# Main_Titan_V3.net
KiCad netlist of a schematic drawn in EAGLE
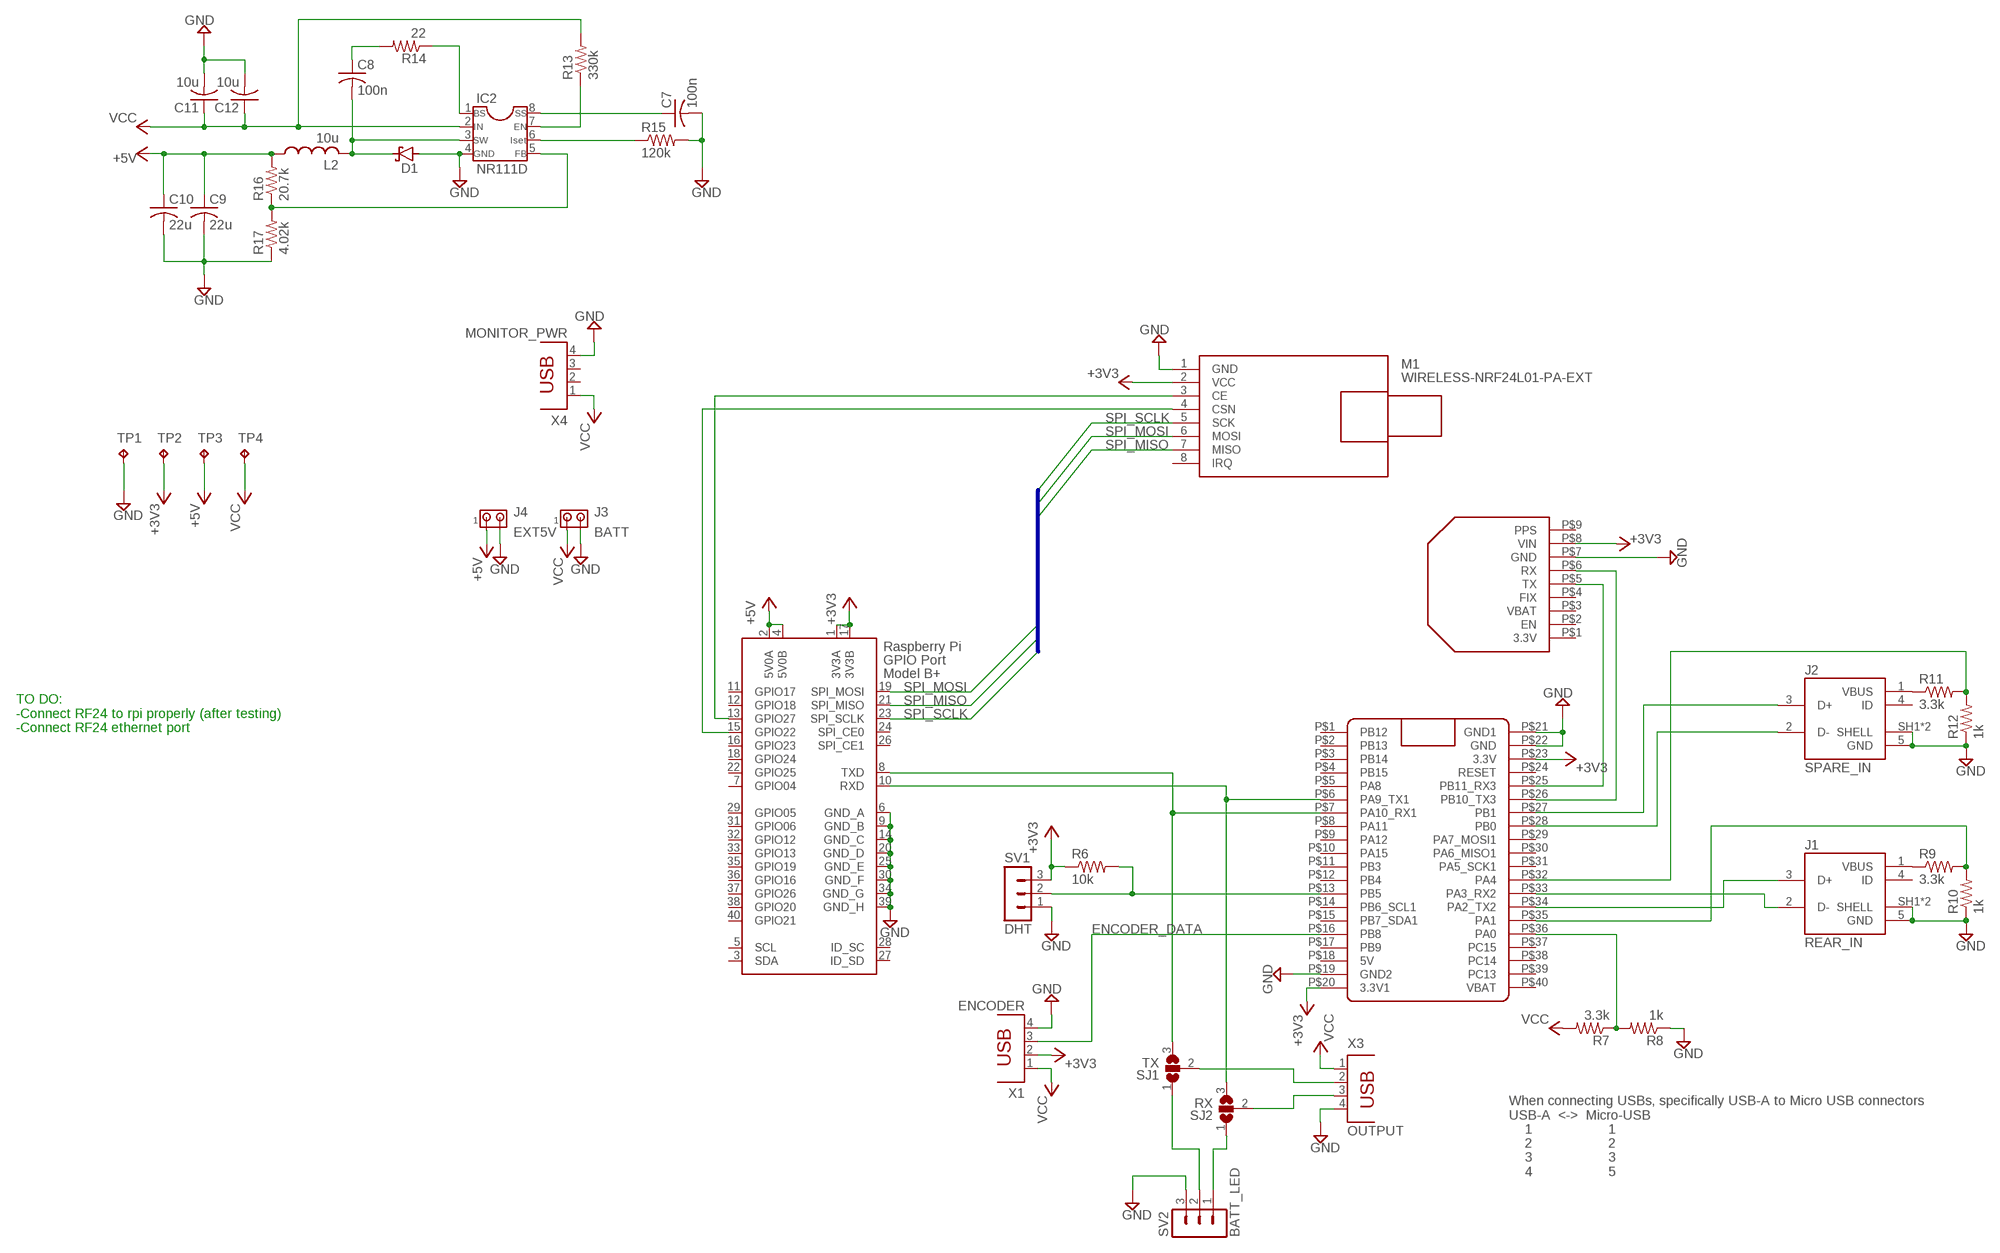
[diagram p0: schematic, sheet 1]

(export (version "E")
  (design (tool "Eeschema 10.0.6"))
  (components
    (comp (ref "C7")
      (value "100n")
      (footprint "eagle-import:C050-024X044")
      (libsource (lib "eagle-import") (part "C-US050-024X044"))
    )
    (comp (ref "C8")
      (value "100n")
      (footprint "eagle-import:C050-024X044")
      (libsource (lib "eagle-import") (part "C-US050-024X044"))
    )
    (comp (ref "C9")
      (value "22u")
      (footprint "eagle-import:C025-024X044")
      (libsource (lib "eagle-import") (part "C-US025-024X044"))
    )
    (comp (ref "C10")
      (value "22u")
      (footprint "eagle-import:C025-024X044")
      (libsource (lib "eagle-import") (part "C-US025-024X044"))
    )
    (comp (ref "C11")
      (value "10u")
      (footprint "eagle-import:C025-024X044")
      (libsource (lib "eagle-import") (part "C-US025-024X044"))
    )
    (comp (ref "C12")
      (value "10u")
      (footprint "eagle-import:C025-024X044")
      (libsource (lib "eagle-import") (part "C-US025-024X044"))
    )
    (comp (ref "D1")
      (value "SCHOTTKY-DIODEC4111-15")
      (footprint "eagle-import:C4111-15")
      (libsource (lib "eagle-import") (part "SCHOTTKY-DIODEC4111-15"))
    )
    (comp (ref "IC2")
      (value "NR111D")
      (footprint "eagle-import:DIL08")
      (libsource (lib "eagle-import") (part "DIL8"))
    )
    (comp (ref "J1")
      (value "REAR_IN")
      (footprint "eagle-import:TE_2172034-1")
      (fields
        (field (name "COMMENT") "2172034-1")
        (field (name "DIGI-KEY_PART_NUMBER") "A135698-ND")
        (field (name "MF") "TE Connectivity")
      )
      (libsource (lib "eagle-import") (part "2172034-1"))
    )
    (comp (ref "J2")
      (value "SPARE_IN")
      (footprint "eagle-import:TE_2172034-1")
      (fields
        (field (name "COMMENT") "2172034-1")
        (field (name "DIGI-KEY_PART_NUMBER") "A135698-ND")
        (field (name "MF") "TE Connectivity")
      )
      (libsource (lib "eagle-import") (part "2172034-1"))
    )
    (comp (ref "J3")
      (value "BATT")
      (footprint "eagle-import:1X2MTA")
      (libsource (lib "eagle-import") (part "MTA02-156"))
    )
    (comp (ref "J4")
      (value "EXT5V")
      (footprint "eagle-import:1X2MTA")
      (libsource (lib "eagle-import") (part "MTA02-156"))
    )
    (comp (ref "L2")
      (value "10u")
      (footprint "eagle-import:INDRD650W105D880H1100B")
      (libsource (lib "eagle-import") (part "WURTHINDUCTOR1"))
    )
    (comp (ref "M1")
      (value "WIRELESS-NRF24L01-PA-EXT")
      (footprint "eagle-import:WIRELESS-NRF24L01-PA-EXT")
      (libsource (lib "eagle-import") (part "WIRELESS-NRF24L01-PA-EXT"))
    )
    (comp (ref "R6")
      (value "10k")
      (footprint "eagle-import:0204_7")
      (libsource (lib "eagle-import") (part "R-US_0204/7"))
    )
    (comp (ref "R7")
      (value "3.3k")
      (footprint "eagle-import:0204_7")
      (libsource (lib "eagle-import") (part "R-US_0204/7"))
    )
    (comp (ref "R8")
      (value "1k")
      (footprint "eagle-import:0204_7")
      (libsource (lib "eagle-import") (part "R-US_0204/7"))
    )
    (comp (ref "R9")
      (value "3.3k")
      (footprint "eagle-import:0204_7")
      (libsource (lib "eagle-import") (part "R-US_0204/7"))
    )
    (comp (ref "R10")
      (value "1k")
      (footprint "eagle-import:0204_7")
      (libsource (lib "eagle-import") (part "R-US_0204/7"))
    )
    (comp (ref "R11")
      (value "3.3k")
      (footprint "eagle-import:0204_7")
      (libsource (lib "eagle-import") (part "R-US_0204/7"))
    )
    (comp (ref "R12")
      (value "1k")
      (footprint "eagle-import:0204_7")
      (libsource (lib "eagle-import") (part "R-US_0204/7"))
    )
    (comp (ref "R13")
      (value "330k")
      (footprint "eagle-import:0204_7")
      (libsource (lib "eagle-import") (part "R-US_0204/7"))
    )
    (comp (ref "R14")
      (value "22")
      (footprint "eagle-import:0204_7")
      (libsource (lib "eagle-import") (part "R-US_0204/7"))
    )
    (comp (ref "R15")
      (value "120k")
      (footprint "eagle-import:0204_7")
      (libsource (lib "eagle-import") (part "R-US_0204/7"))
    )
    (comp (ref "R16")
      (value "20.7k")
      (footprint "eagle-import:0204_7")
      (libsource (lib "eagle-import") (part "R-US_0204/7"))
    )
    (comp (ref "R17")
      (value "4.02k")
      (footprint "eagle-import:0204_7")
      (libsource (lib "eagle-import") (part "R-US_0204/7"))
    )
    (comp (ref "SJ1")
      (value "TX")
      (footprint "eagle-import:SJ_2")
      (libsource (lib "eagle-import") (part "SJ2W"))
    )
    (comp (ref "SJ2")
      (value "RX")
      (footprint "eagle-import:SJ_2")
      (libsource (lib "eagle-import") (part "SJ2W"))
    )
    (comp (ref "SV1")
      (value "DHT")
      (footprint "eagle-import:MA03-1")
      (libsource (lib "eagle-import") (part "MA03-1"))
    )
    (comp (ref "SV2")
      (value "BATT_LED")
      (footprint "eagle-import:MA03-1")
      (libsource (lib "eagle-import") (part "MA03-1"))
    )
    (comp (ref "TP1")
      (value "GND")
      (footprint "eagle-import:TP20SQ")
      (libsource (lib "eagle-import") (part "TPTP20SQ"))
    )
    (comp (ref "TP2")
      (value "3V3")
      (footprint "eagle-import:TP20SQ")
      (libsource (lib "eagle-import") (part "TPTP20SQ"))
    )
    (comp (ref "TP3")
      (value "5V")
      (footprint "eagle-import:TP20SQ")
      (libsource (lib "eagle-import") (part "TPTP20SQ"))
    )
    (comp (ref "TP4")
      (value "BAT")
      (footprint "eagle-import:TP20SQ")
      (libsource (lib "eagle-import") (part "TPTP20SQ"))
    )
    (comp (ref "U$1")
      (value "BLUE_PILL")
      (footprint "eagle-import:BLUE_PILL")
      (libsource (lib "eagle-import") (part "BLUE_PILL"))
    )
    (comp (ref "U$2")
      (value "ULTIMATE-GPS")
      (footprint "eagle-import:ULTIMATE_GPS")
      (libsource (lib "eagle-import") (part "ULTIMATE-GPS"))
    )
    (comp (ref "X1")
      (value "ENCODER")
      (footprint "eagle-import:PN87520")
      (libsource (lib "eagle-import") (part "PN87520"))
    )
    (comp (ref "X2")
      (value "RPI")
      (footprint "eagle-import:RASPI_GPIO_B+_BOX")
      (libsource (lib "eagle-import") (part "RASPI_GPIO_B+#_BOX"))
    )
    (comp (ref "X3")
      (value "OUTPUT")
      (footprint "eagle-import:PN87520")
      (libsource (lib "eagle-import") (part "PN87520"))
    )
    (comp (ref "X4")
      (value "MONITOR_PWR")
      (footprint "eagle-import:PN87520")
      (libsource (lib "eagle-import") (part "PN87520"))
    )
  )
  (nets
    (net (code "1") (name "+3V3") (class "Default")
      (node (ref "M1") (pin "2") (pinfunction "VCC_2") (pintype "power_in"))
      (node (ref "R6") (pin "1") (pinfunction "1_1") (pintype "passive"))
      (node (ref "SV1") (pin "3") (pinfunction "3_3") (pintype "passive"))
      (node (ref "TP2") (pin "TP") (pinfunction "TP_TP") (pintype "input"))
      (node (ref "U$1") (pin "P$20") (pinfunction "3.3V1_P$20") (pintype "power_in"))
      (node (ref "U$1") (pin "P$23") (pinfunction "3.3V_P$23") (pintype "power_in"))
      (node (ref "U$2") (pin "P$8") (pinfunction "VIN_P$8") (pintype "bidirectional"))
      (node (ref "X1") (pin "2") (pinfunction "2_2") (pintype "passive"))
      (node (ref "X2") (pin "1") (pinfunction "3V3A_1") (pintype "power_in"))
      (node (ref "X2") (pin "17") (pinfunction "3V3B_17") (pintype "power_in"))
    )
    (net (code "2") (name "+5V") (class "Default")
      (node (ref "C10") (pin "1") (pinfunction "1_1") (pintype "passive"))
      (node (ref "C9") (pin "1") (pinfunction "1_1") (pintype "passive"))
      (node (ref "J4") (pin "1") (pinfunction "1_1") (pintype "passive"))
      (node (ref "L2") (pin "1") (pinfunction "1_1") (pintype "passive"))
      (node (ref "R16") (pin "2") (pinfunction "2_2") (pintype "passive"))
      (node (ref "TP3") (pin "TP") (pinfunction "TP_TP") (pintype "input"))
      (node (ref "X2") (pin "2") (pinfunction "5V0A_2") (pintype "power_in"))
      (node (ref "X2") (pin "4") (pinfunction "5V0B_4") (pintype "power_in"))
    )
    (net (code "3") (name "/3.3V") (class "Default")
      (node (ref "U$2") (pin "P$1") (pinfunction "3.3V_P$1") (pintype "power_in"))
    )
    (net (code "4") (name "/ENCODER_DATA") (class "Default")
      (node (ref "U$1") (pin "P$16") (pinfunction "PB8_P$16") (pintype "bidirectional"))
      (node (ref "X1") (pin "3") (pinfunction "3_3") (pintype "passive"))
    )
    (net (code "5") (name "/SPI_MISO") (class "Default")
      (node (ref "M1") (pin "7") (pinfunction "MISO_7") (pintype "bidirectional"))
      (node (ref "X2") (pin "21") (pinfunction "SPI_MISO_21") (pintype "bidirectional"))
    )
    (net (code "6") (name "/SPI_MOSI") (class "Default")
      (node (ref "M1") (pin "6") (pinfunction "MOSI_6") (pintype "bidirectional"))
      (node (ref "X2") (pin "19") (pinfunction "SPI_MOSI_19") (pintype "bidirectional"))
    )
    (net (code "7") (name "/SPI_SCLK") (class "Default")
      (node (ref "M1") (pin "5") (pinfunction "SCK_5") (pintype "bidirectional"))
      (node (ref "X2") (pin "23") (pinfunction "SPI_SCLK_23") (pintype "bidirectional"))
    )
    (net (code "8") (name "GND") (class "Default")
      (node (ref "C10") (pin "2") (pinfunction "2_2") (pintype "passive"))
      (node (ref "C11") (pin "2") (pinfunction "2_2") (pintype "passive"))
      (node (ref "C12") (pin "2") (pinfunction "2_2") (pintype "passive"))
      (node (ref "C7") (pin "2") (pinfunction "2_2") (pintype "passive"))
      (node (ref "C9") (pin "2") (pinfunction "2_2") (pintype "passive"))
      (node (ref "D1") (pin "A") (pinfunction "A_A") (pintype "passive"))
      (node (ref "IC2") (pin "4") (pinfunction "GND_4") (pintype "passive"))
      (node (ref "J1") (pin "5") (pinfunction "GND_5") (pintype "power_in"))
      (node (ref "J1") (pin "SH1") (pinfunction "SHELL_SH1") (pintype "power_in"))
      (node (ref "J1") (pin "SH2") (pinfunction "SHELL_SH2") (pintype "power_in"))
      (node (ref "J2") (pin "5") (pinfunction "GND_5") (pintype "power_in"))
      (node (ref "J2") (pin "SH1") (pinfunction "SHELL_SH1") (pintype "power_in"))
      (node (ref "J2") (pin "SH2") (pinfunction "SHELL_SH2") (pintype "power_in"))
      (node (ref "J3") (pin "2") (pinfunction "2_2") (pintype "passive"))
      (node (ref "J4") (pin "2") (pinfunction "2_2") (pintype "passive"))
      (node (ref "M1") (pin "1") (pinfunction "GND_1") (pintype "power_in"))
      (node (ref "R10") (pin "1") (pinfunction "1_1") (pintype "passive"))
      (node (ref "R12") (pin "1") (pinfunction "1_1") (pintype "passive"))
      (node (ref "R15") (pin "2") (pinfunction "2_2") (pintype "passive"))
      (node (ref "R17") (pin "1") (pinfunction "1_1") (pintype "passive"))
      (node (ref "R8") (pin "1") (pinfunction "1_1") (pintype "passive"))
      (node (ref "SV1") (pin "1") (pinfunction "1_1") (pintype "passive"))
      (node (ref "SV2") (pin "3") (pinfunction "3_3") (pintype "passive"))
      (node (ref "TP1") (pin "TP") (pinfunction "TP_TP") (pintype "input"))
      (node (ref "U$1") (pin "P$19") (pinfunction "GND2_P$19") (pintype "bidirectional"))
      (node (ref "U$1") (pin "P$21") (pinfunction "GND1_P$21") (pintype "power_in"))
      (node (ref "U$1") (pin "P$22") (pinfunction "GND_P$22") (pintype "bidirectional"))
      (node (ref "U$2") (pin "P$7") (pinfunction "GND_P$7") (pintype "power_in"))
      (node (ref "X1") (pin "4") (pinfunction "4_4") (pintype "passive"))
      (node (ref "X2") (pin "14") (pinfunction "GND_C_14") (pintype "power_in"))
      (node (ref "X2") (pin "20") (pinfunction "GND_D_20") (pintype "power_in"))
      (node (ref "X2") (pin "25") (pinfunction "GND_E_25") (pintype "power_in"))
      (node (ref "X2") (pin "30") (pinfunction "GND_F_30") (pintype "power_in"))
      (node (ref "X2") (pin "34") (pinfunction "GND_G_34") (pintype "power_in"))
      (node (ref "X2") (pin "39") (pinfunction "GND_H_39") (pintype "power_in"))
      (node (ref "X2") (pin "6") (pinfunction "GND_A_6") (pintype "power_in"))
      (node (ref "X2") (pin "9") (pinfunction "GND_B_9") (pintype "power_in"))
      (node (ref "X3") (pin "4") (pinfunction "4_4") (pintype "passive"))
      (node (ref "X4") (pin "4") (pinfunction "4_4") (pintype "passive"))
    )
    (net (code "9") (name "Net-(C8-Pad1)") (class "Default")
      (node (ref "C8") (pin "1") (pinfunction "1_1") (pintype "passive"))
      (node (ref "R14") (pin "2") (pinfunction "2_2") (pintype "passive"))
    )
    (net (code "10") (name "Net-(IC2-BS)") (class "Default")
      (node (ref "IC2") (pin "1") (pinfunction "BS_1") (pintype "passive"))
      (node (ref "R14") (pin "1") (pinfunction "1_1") (pintype "passive"))
    )
    (net (code "11") (name "Net-(IC2-EN)") (class "Default")
      (node (ref "IC2") (pin "7") (pinfunction "EN_7") (pintype "passive"))
      (node (ref "R13") (pin "1") (pinfunction "1_1") (pintype "passive"))
    )
    (net (code "12") (name "Net-(IC2-FB)") (class "Default")
      (node (ref "IC2") (pin "5") (pinfunction "FB_5") (pintype "passive"))
      (node (ref "R16") (pin "1") (pinfunction "1_1") (pintype "passive"))
      (node (ref "R17") (pin "2") (pinfunction "2_2") (pintype "passive"))
    )
    (net (code "13") (name "Net-(IC2-ISET)") (class "Default")
      (node (ref "IC2") (pin "6") (pinfunction "ISET_6") (pintype "passive"))
      (node (ref "R15") (pin "1") (pinfunction "1_1") (pintype "passive"))
    )
    (net (code "14") (name "Net-(IC2-SS)") (class "Default")
      (node (ref "C7") (pin "1") (pinfunction "1_1") (pintype "passive"))
      (node (ref "IC2") (pin "8") (pinfunction "SS_8") (pintype "passive"))
    )
    (net (code "15") (name "Net-(IC2-SW)") (class "Default")
      (node (ref "C8") (pin "2") (pinfunction "2_2") (pintype "passive"))
      (node (ref "D1") (pin "C") (pinfunction "C_C") (pintype "passive"))
      (node (ref "IC2") (pin "3") (pinfunction "SW_3") (pintype "passive"))
      (node (ref "L2") (pin "2") (pinfunction "2_2") (pintype "passive"))
    )
    (net (code "16") (name "Net-(J1-D+)") (class "Default")
      (node (ref "J1") (pin "3") (pinfunction "D+_3") (pintype "bidirectional"))
      (node (ref "U$1") (pin "P$34") (pinfunction "PA2_TX2_P$34") (pintype "bidirectional"))
    )
    (net (code "17") (name "Net-(J1-D-)") (class "Default")
      (node (ref "J1") (pin "2") (pinfunction "D-_2") (pintype "bidirectional"))
      (node (ref "U$1") (pin "P$33") (pinfunction "PA3_RX2_P$33") (pintype "bidirectional"))
    )
    (net (code "18") (name "Net-(J1-VBUS)") (class "Default")
      (node (ref "J1") (pin "1") (pinfunction "VBUS_1") (pintype "power_in"))
      (node (ref "R9") (pin "1") (pinfunction "1_1") (pintype "passive"))
    )
    (net (code "19") (name "Net-(J2-D+)") (class "Default")
      (node (ref "J2") (pin "3") (pinfunction "D+_3") (pintype "bidirectional"))
      (node (ref "U$1") (pin "P$27") (pinfunction "PB1_P$27") (pintype "bidirectional"))
    )
    (net (code "20") (name "Net-(J2-D-)") (class "Default")
      (node (ref "J2") (pin "2") (pinfunction "D-_2") (pintype "bidirectional"))
      (node (ref "U$1") (pin "P$28") (pinfunction "PB0_P$28") (pintype "bidirectional"))
    )
    (net (code "21") (name "Net-(J2-VBUS)") (class "Default")
      (node (ref "J2") (pin "1") (pinfunction "VBUS_1") (pintype "power_in"))
      (node (ref "R11") (pin "1") (pinfunction "1_1") (pintype "passive"))
    )
    (net (code "22") (name "Net-(M1-CE)") (class "Default")
      (node (ref "M1") (pin "3") (pinfunction "CE_3") (pintype "bidirectional"))
      (node (ref "X2") (pin "13") (pinfunction "GPIO27_13") (pintype "bidirectional"))
    )
    (net (code "23") (name "Net-(M1-CSN)") (class "Default")
      (node (ref "M1") (pin "4") (pinfunction "CSN_4") (pintype "bidirectional"))
      (node (ref "X2") (pin "15") (pinfunction "GPIO22_15") (pintype "bidirectional"))
    )
    (net (code "24") (name "Net-(SJ1-Pad1)") (class "Default")
      (node (ref "SJ1") (pin "1") (pinfunction "1_1") (pintype "passive"))
      (node (ref "SV2") (pin "2") (pinfunction "2_2") (pintype "passive"))
    )
    (net (code "25") (name "Net-(SJ1-Pad2)") (class "Default")
      (node (ref "SJ1") (pin "2") (pinfunction "2_2") (pintype "passive"))
      (node (ref "X3") (pin "2") (pinfunction "2_2") (pintype "passive"))
    )
    (net (code "26") (name "Net-(SJ2-Pad1)") (class "Default")
      (node (ref "SJ2") (pin "1") (pinfunction "1_1") (pintype "passive"))
      (node (ref "SV2") (pin "1") (pinfunction "1_1") (pintype "passive"))
    )
    (net (code "27") (name "Net-(SJ2-Pad2)") (class "Default")
      (node (ref "SJ2") (pin "2") (pinfunction "2_2") (pintype "passive"))
      (node (ref "X3") (pin "3") (pinfunction "3_3") (pintype "passive"))
    )
    (net (code "28") (name "Net-(U$1-PA0)") (class "Default")
      (node (ref "R7") (pin "1") (pinfunction "1_1") (pintype "passive"))
      (node (ref "R8") (pin "2") (pinfunction "2_2") (pintype "passive"))
      (node (ref "U$1") (pin "P$36") (pinfunction "PA0_P$36") (pintype "bidirectional"))
    )
    (net (code "29") (name "Net-(U$1-PA1)") (class "Default")
      (node (ref "R10") (pin "2") (pinfunction "2_2") (pintype "passive"))
      (node (ref "R9") (pin "2") (pinfunction "2_2") (pintype "passive"))
      (node (ref "U$1") (pin "P$35") (pinfunction "PA1_P$35") (pintype "bidirectional"))
    )
    (net (code "30") (name "Net-(U$1-PA4)") (class "Default")
      (node (ref "R11") (pin "2") (pinfunction "2_2") (pintype "passive"))
      (node (ref "R12") (pin "2") (pinfunction "2_2") (pintype "passive"))
      (node (ref "U$1") (pin "P$32") (pinfunction "PA4_P$32") (pintype "bidirectional"))
    )
    (net (code "31") (name "Net-(U$1-PA9_TX1)") (class "Default")
      (node (ref "SJ2") (pin "3") (pinfunction "3_3") (pintype "passive"))
      (node (ref "U$1") (pin "P$6") (pinfunction "PA9_TX1_P$6") (pintype "bidirectional"))
      (node (ref "X2") (pin "10") (pinfunction "RXD_10") (pintype "bidirectional"))
    )
    (net (code "32") (name "Net-(U$1-PA10_RX1)") (class "Default")
      (node (ref "SJ1") (pin "3") (pinfunction "3_3") (pintype "passive"))
      (node (ref "U$1") (pin "P$7") (pinfunction "PA10_RX1_P$7") (pintype "bidirectional"))
      (node (ref "X2") (pin "8") (pinfunction "TXD_8") (pintype "bidirectional"))
    )
    (net (code "33") (name "Net-(U$1-PB5)") (class "Default")
      (node (ref "R6") (pin "2") (pinfunction "2_2") (pintype "passive"))
      (node (ref "SV1") (pin "2") (pinfunction "2_2") (pintype "passive"))
      (node (ref "U$1") (pin "P$13") (pinfunction "PB5_P$13") (pintype "bidirectional"))
    )
    (net (code "34") (name "Net-(U$1-PB10_TX3)") (class "Default")
      (node (ref "U$1") (pin "P$26") (pinfunction "PB10_TX3_P$26") (pintype "bidirectional"))
      (node (ref "U$2") (pin "P$6") (pinfunction "RX_P$6") (pintype "bidirectional"))
    )
    (net (code "35") (name "Net-(U$1-PB11_RX3)") (class "Default")
      (node (ref "U$1") (pin "P$25") (pinfunction "PB11_RX3_P$25") (pintype "bidirectional"))
      (node (ref "U$2") (pin "P$5") (pinfunction "TX_P$5") (pintype "bidirectional"))
    )
    (net (code "36") (name "VCC") (class "Default")
      (node (ref "C11") (pin "1") (pinfunction "1_1") (pintype "passive"))
      (node (ref "C12") (pin "1") (pinfunction "1_1") (pintype "passive"))
      (node (ref "IC2") (pin "2") (pinfunction "IN_2") (pintype "passive"))
      (node (ref "J3") (pin "1") (pinfunction "1_1") (pintype "passive"))
      (node (ref "R13") (pin "2") (pinfunction "2_2") (pintype "passive"))
      (node (ref "R7") (pin "2") (pinfunction "2_2") (pintype "passive"))
      (node (ref "TP4") (pin "TP") (pinfunction "TP_TP") (pintype "input"))
      (node (ref "X1") (pin "1") (pinfunction "1_1") (pintype "passive"))
      (node (ref "X3") (pin "1") (pinfunction "1_1") (pintype "passive"))
      (node (ref "X4") (pin "1") (pinfunction "1_1") (pintype "passive"))
    )
    (net (code "37") (name "unconnected-(J1-ID-Pad4)") (class "Default")
      (node (ref "J1") (pin "4") (pinfunction "ID_4") (pintype "passive"))
    )
    (net (code "38") (name "unconnected-(J2-ID-Pad4)") (class "Default")
      (node (ref "J2") (pin "4") (pinfunction "ID_4") (pintype "passive"))
    )
    (net (code "39") (name "unconnected-(M1-IRQ-Pad8)") (class "Default")
      (node (ref "M1") (pin "8") (pinfunction "IRQ_8") (pintype "bidirectional"))
    )
    (net (code "40") (name "unconnected-(U$1-5V-PadP$18)") (class "Default")
      (node (ref "U$1") (pin "P$18") (pinfunction "5V_P$18") (pintype "bidirectional"))
    )
    (net (code "41") (name "unconnected-(U$1-PA5_SCK1-PadP$31)") (class "Default")
      (node (ref "U$1") (pin "P$31") (pinfunction "PA5_SCK1_P$31") (pintype "bidirectional"))
    )
    (net (code "42") (name "unconnected-(U$1-PA6_MISO1-PadP$30)") (class "Default")
      (node (ref "U$1") (pin "P$30") (pinfunction "PA6_MISO1_P$30") (pintype "bidirectional"))
    )
    (net (code "43") (name "unconnected-(U$1-PA7_MOSI1-PadP$29)") (class "Default")
      (node (ref "U$1") (pin "P$29") (pinfunction "PA7_MOSI1_P$29") (pintype "bidirectional"))
    )
    (net (code "44") (name "unconnected-(U$1-PA8-PadP$5)") (class "Default")
      (node (ref "U$1") (pin "P$5") (pinfunction "PA8_P$5") (pintype "bidirectional"))
    )
    (net (code "45") (name "unconnected-(U$1-PA11-PadP$8)") (class "Default")
      (node (ref "U$1") (pin "P$8") (pinfunction "PA11_P$8") (pintype "bidirectional"))
    )
    (net (code "46") (name "unconnected-(U$1-PA12-PadP$9)") (class "Default")
      (node (ref "U$1") (pin "P$9") (pinfunction "PA12_P$9") (pintype "bidirectional"))
    )
    (net (code "47") (name "unconnected-(U$1-PA15-PadP$10)") (class "Default")
      (node (ref "U$1") (pin "P$10") (pinfunction "PA15_P$10") (pintype "bidirectional"))
    )
    (net (code "48") (name "unconnected-(U$1-PB3-PadP$11)") (class "Default")
      (node (ref "U$1") (pin "P$11") (pinfunction "PB3_P$11") (pintype "bidirectional"))
    )
    (net (code "49") (name "unconnected-(U$1-PB4-PadP$12)") (class "Default")
      (node (ref "U$1") (pin "P$12") (pinfunction "PB4_P$12") (pintype "bidirectional"))
    )
    (net (code "50") (name "unconnected-(U$1-PB6_SCL1-PadP$14)") (class "Default")
      (node (ref "U$1") (pin "P$14") (pinfunction "PB6_SCL1_P$14") (pintype "bidirectional"))
    )
    (net (code "51") (name "unconnected-(U$1-PB7_SDA1-PadP$15)") (class "Default")
      (node (ref "U$1") (pin "P$15") (pinfunction "PB7_SDA1_P$15") (pintype "bidirectional"))
    )
    (net (code "52") (name "unconnected-(U$1-PB9-PadP$17)") (class "Default")
      (node (ref "U$1") (pin "P$17") (pinfunction "PB9_P$17") (pintype "bidirectional"))
    )
    (net (code "53") (name "unconnected-(U$1-PB12-PadP$1)") (class "Default")
      (node (ref "U$1") (pin "P$1") (pinfunction "PB12_P$1") (pintype "bidirectional"))
    )
    (net (code "54") (name "unconnected-(U$1-PB13-PadP$2)") (class "Default")
      (node (ref "U$1") (pin "P$2") (pinfunction "PB13_P$2") (pintype "bidirectional"))
    )
    (net (code "55") (name "unconnected-(U$1-PB14-PadP$3)") (class "Default")
      (node (ref "U$1") (pin "P$3") (pinfunction "PB14_P$3") (pintype "bidirectional"))
    )
    (net (code "56") (name "unconnected-(U$1-PB15-PadP$4)") (class "Default")
      (node (ref "U$1") (pin "P$4") (pinfunction "PB15_P$4") (pintype "bidirectional"))
    )
    (net (code "57") (name "unconnected-(U$1-PC13-PadP$39)") (class "Default")
      (node (ref "U$1") (pin "P$39") (pinfunction "PC13_P$39") (pintype "bidirectional"))
    )
    (net (code "58") (name "unconnected-(U$1-PC14-PadP$38)") (class "Default")
      (node (ref "U$1") (pin "P$38") (pinfunction "PC14_P$38") (pintype "bidirectional"))
    )
    (net (code "59") (name "unconnected-(U$1-PC15-PadP$37)") (class "Default")
      (node (ref "U$1") (pin "P$37") (pinfunction "PC15_P$37") (pintype "bidirectional"))
    )
    (net (code "60") (name "unconnected-(U$1-RESET-PadP$24)") (class "Default")
      (node (ref "U$1") (pin "P$24") (pinfunction "RESET_P$24") (pintype "bidirectional"))
    )
    (net (code "61") (name "unconnected-(U$1-VBAT-PadP$40)") (class "Default")
      (node (ref "U$1") (pin "P$40") (pinfunction "VBAT_P$40") (pintype "bidirectional"))
    )
    (net (code "62") (name "unconnected-(U$2-EN-PadP$2)") (class "Default")
      (node (ref "U$2") (pin "P$2") (pinfunction "EN_P$2") (pintype "bidirectional"))
    )
    (net (code "63") (name "unconnected-(U$2-FIX-PadP$4)") (class "Default")
      (node (ref "U$2") (pin "P$4") (pinfunction "FIX_P$4") (pintype "bidirectional"))
    )
    (net (code "64") (name "unconnected-(U$2-PPS-PadP$9)") (class "Default")
      (node (ref "U$2") (pin "P$9") (pinfunction "PPS_P$9") (pintype "bidirectional"))
    )
    (net (code "65") (name "unconnected-(U$2-VBAT-PadP$3)") (class "Default")
      (node (ref "U$2") (pin "P$3") (pinfunction "VBAT_P$3") (pintype "bidirectional"))
    )
    (net (code "66") (name "unconnected-(X2-GPIO04-Pad7)") (class "Default")
      (node (ref "X2") (pin "7") (pinfunction "GPIO04_7") (pintype "bidirectional"))
    )
    (net (code "67") (name "unconnected-(X2-GPIO05-Pad29)") (class "Default")
      (node (ref "X2") (pin "29") (pinfunction "GPIO05_29") (pintype "no_connect"))
    )
    (net (code "68") (name "unconnected-(X2-GPIO06-Pad31)") (class "Default")
      (node (ref "X2") (pin "31") (pinfunction "GPIO06_31") (pintype "no_connect"))
    )
    (net (code "69") (name "unconnected-(X2-GPIO12-Pad32)") (class "Default")
      (node (ref "X2") (pin "32") (pinfunction "GPIO12_32") (pintype "no_connect"))
    )
    (net (code "70") (name "unconnected-(X2-GPIO13-Pad33)") (class "Default")
      (node (ref "X2") (pin "33") (pinfunction "GPIO13_33") (pintype "no_connect"))
    )
    (net (code "71") (name "unconnected-(X2-GPIO16-Pad36)") (class "Default")
      (node (ref "X2") (pin "36") (pinfunction "GPIO16_36") (pintype "no_connect"))
    )
    (net (code "72") (name "unconnected-(X2-GPIO17-Pad11)") (class "Default")
      (node (ref "X2") (pin "11") (pinfunction "GPIO17_11") (pintype "bidirectional"))
    )
    (net (code "73") (name "unconnected-(X2-GPIO18-Pad12)") (class "Default")
      (node (ref "X2") (pin "12") (pinfunction "GPIO18_12") (pintype "bidirectional"))
    )
    (net (code "74") (name "unconnected-(X2-GPIO19-Pad35)") (class "Default")
      (node (ref "X2") (pin "35") (pinfunction "GPIO19_35") (pintype "no_connect"))
    )
    (net (code "75") (name "unconnected-(X2-GPIO20-Pad38)") (class "Default")
      (node (ref "X2") (pin "38") (pinfunction "GPIO20_38") (pintype "no_connect"))
    )
    (net (code "76") (name "unconnected-(X2-GPIO21-Pad40)") (class "Default")
      (node (ref "X2") (pin "40") (pinfunction "GPIO21_40") (pintype "no_connect"))
    )
    (net (code "77") (name "unconnected-(X2-GPIO23-Pad16)") (class "Default")
      (node (ref "X2") (pin "16") (pinfunction "GPIO23_16") (pintype "bidirectional"))
    )
    (net (code "78") (name "unconnected-(X2-GPIO24-Pad18)") (class "Default")
      (node (ref "X2") (pin "18") (pinfunction "GPIO24_18") (pintype "bidirectional"))
    )
    (net (code "79") (name "unconnected-(X2-GPIO25-Pad22)") (class "Default")
      (node (ref "X2") (pin "22") (pinfunction "GPIO25_22") (pintype "bidirectional"))
    )
    (net (code "80") (name "unconnected-(X2-GPIO26-Pad37)") (class "Default")
      (node (ref "X2") (pin "37") (pinfunction "GPIO26_37") (pintype "no_connect"))
    )
    (net (code "81") (name "unconnected-(X2-ID_SC-Pad28)") (class "Default")
      (node (ref "X2") (pin "28") (pinfunction "ID_SC_28") (pintype "no_connect"))
    )
    (net (code "82") (name "unconnected-(X2-ID_SD-Pad27)") (class "Default")
      (node (ref "X2") (pin "27") (pinfunction "ID_SD_27") (pintype "no_connect"))
    )
    (net (code "83") (name "unconnected-(X2-SCL-Pad5)") (class "Default")
      (node (ref "X2") (pin "5") (pinfunction "SCL_5") (pintype "bidirectional"))
    )
    (net (code "84") (name "unconnected-(X2-SDA-Pad3)") (class "Default")
      (node (ref "X2") (pin "3") (pinfunction "SDA_3") (pintype "bidirectional"))
    )
    (net (code "85") (name "unconnected-(X2-SPI_CE0-Pad24)") (class "Default")
      (node (ref "X2") (pin "24") (pinfunction "SPI_CE0_24") (pintype "bidirectional"))
    )
    (net (code "86") (name "unconnected-(X2-SPI_CE1-Pad26)") (class "Default")
      (node (ref "X2") (pin "26") (pinfunction "SPI_CE1_26") (pintype "bidirectional"))
    )
    (net (code "87") (name "unconnected-(X4-Pad2)") (class "Default")
      (node (ref "X4") (pin "2") (pinfunction "2_2") (pintype "passive"))
    )
    (net (code "88") (name "unconnected-(X4-Pad3)") (class "Default")
      (node (ref "X4") (pin "3") (pinfunction "3_3") (pintype "passive"))
    )
  )
)
